# LCD.net
KiCad netlist of a schematic drawn in Altium Designer
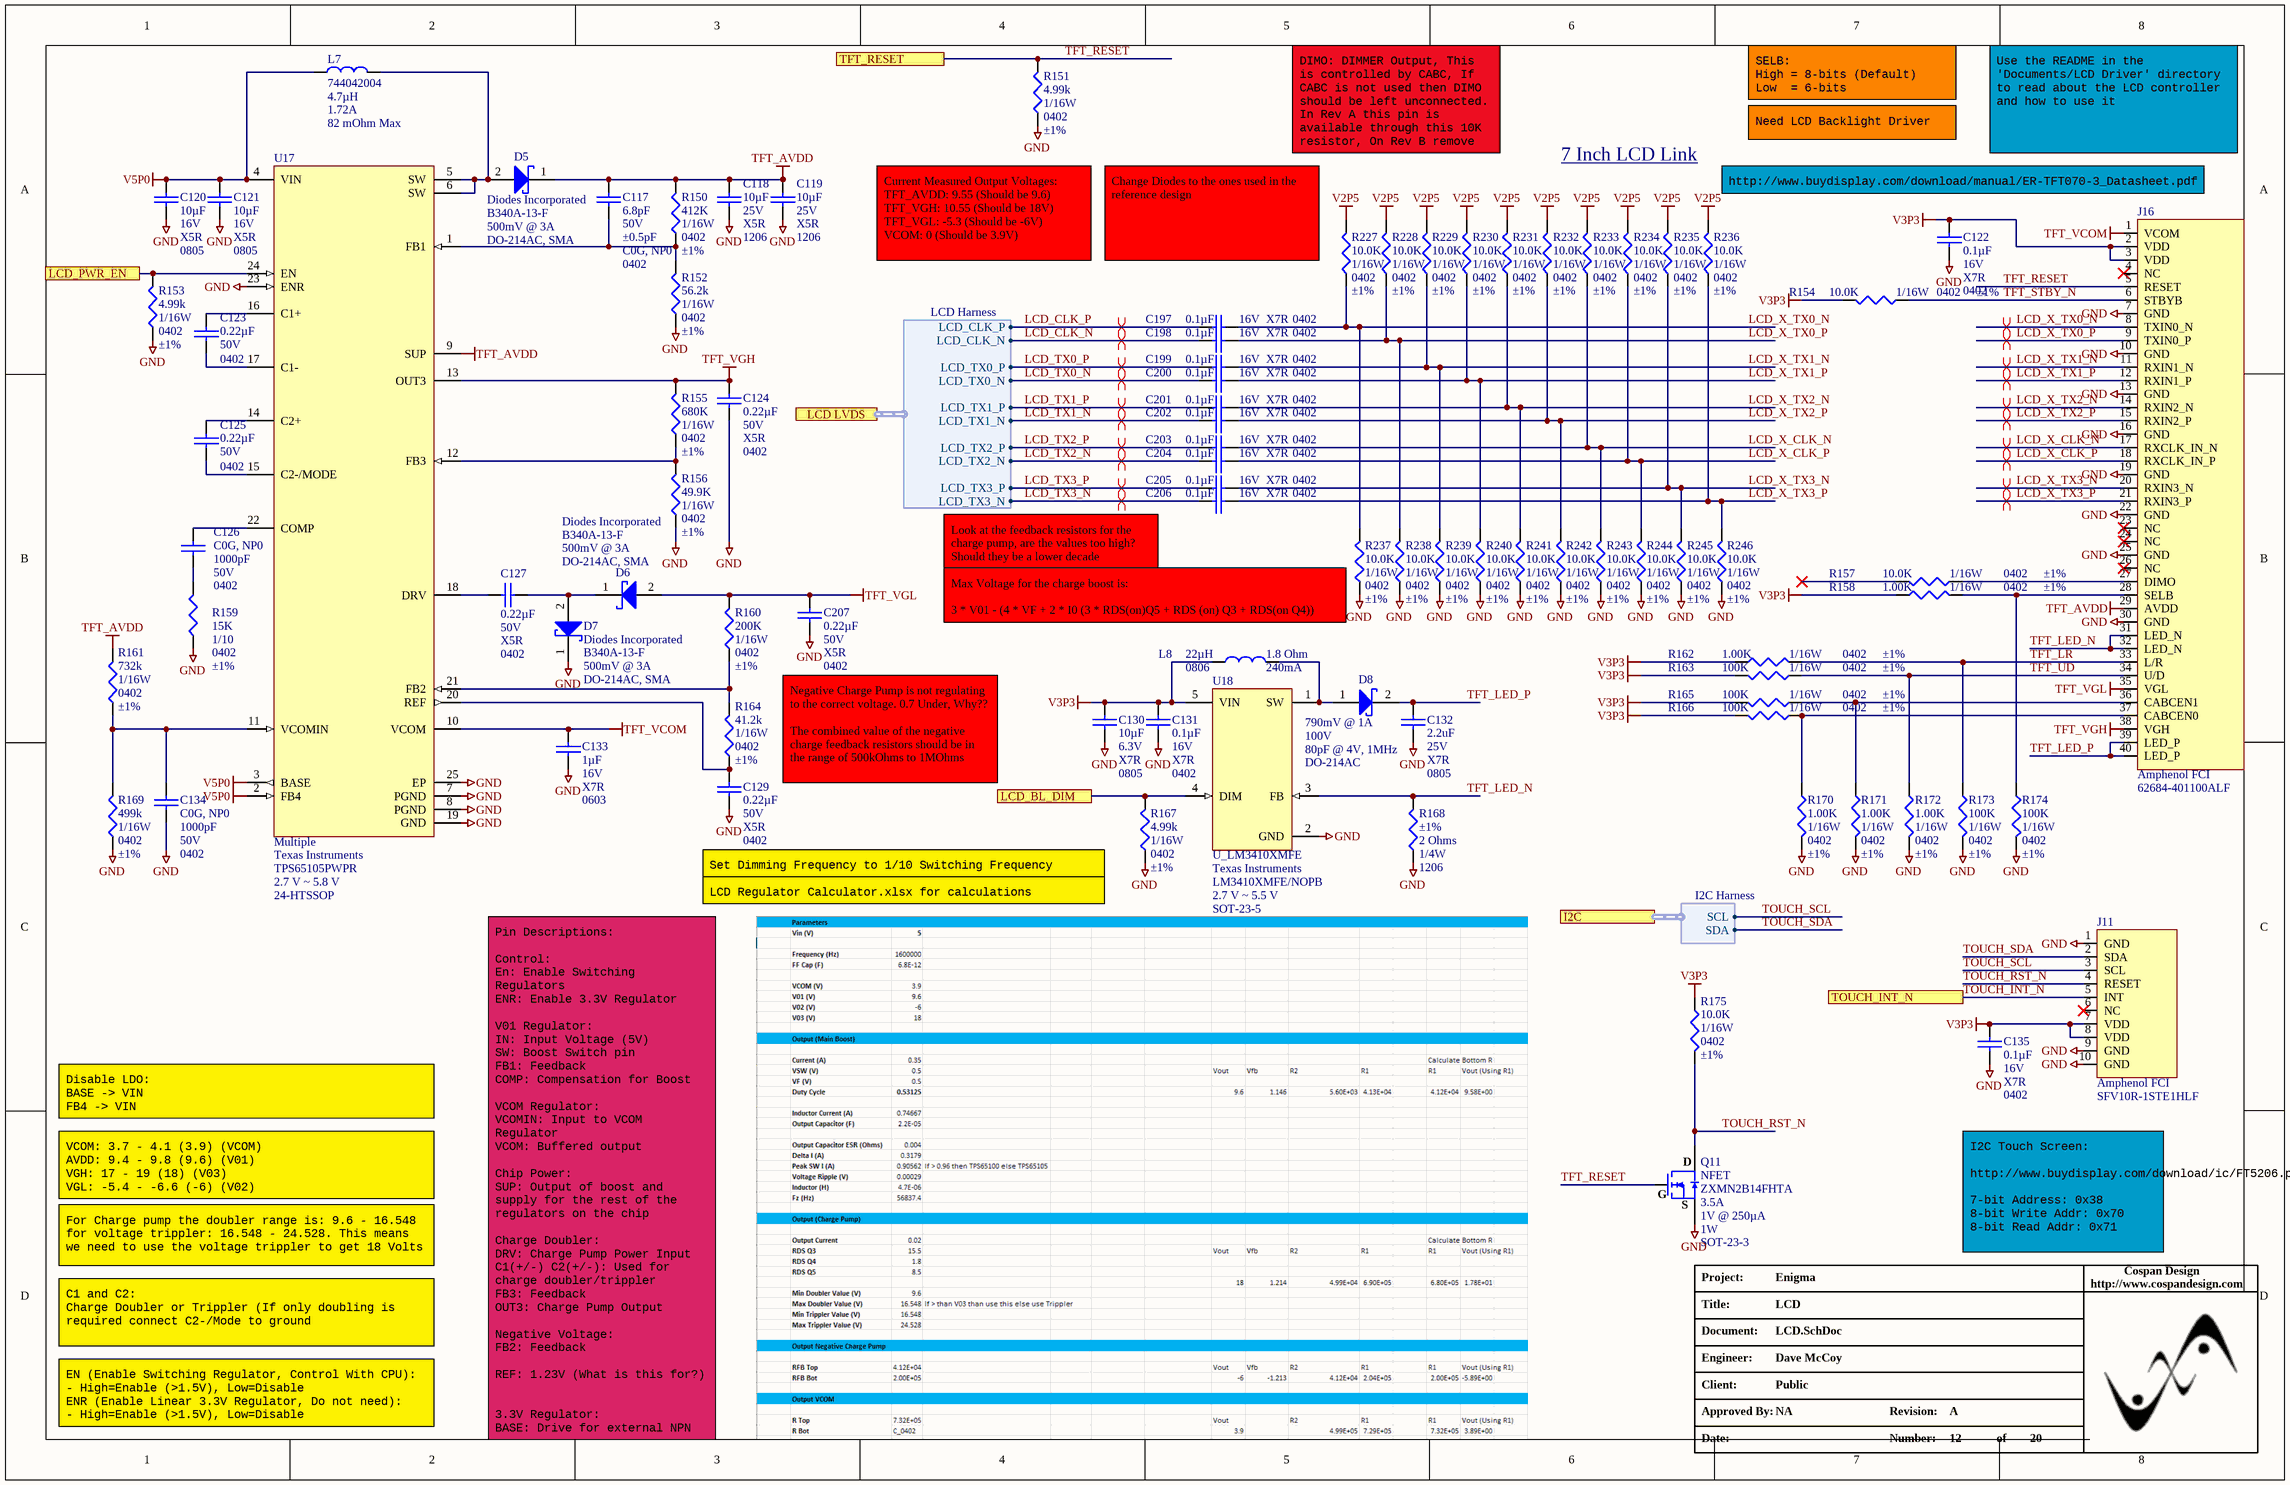
[diagram p0: LCD.SchDoc]

(export (version "E")
  (design (tool "Eeschema 10.0.6"))
  (components
    (comp (ref "C117")
      (value "6.8pF")
      (footprint "C_ERA-0402")
      (description "CAP CER 6.8PF 50V NP0 0402")
      (fields
        (field (name "MANUFACTURER") "Yageo")
        (field (name "MANUFACTURER PART NUMBER") "CC0402DRNPO9BN6R8")
        (field (name "CAPACITANCE") "6.8pF")
        (field (name "VOLTAGE - RATED") "50V")
        (field (name "TOLERANCE") "±0.5pF")
        (field (name "TEMPERATURE COEFFICIENT") "C0G, NP0")
        (field (name "PACKAGE / CASE") "0402")
      )
      (libsource (lib "Main LibraryX") (part "C_0402_6.8PF_50V"))
    )
    (comp (ref "C118")
      (value "10µF")
      (footprint "CAP-1206")
      (description "CAP CER 10UF 25V X5R 1206")
      (fields
        (field (name "MANUFACTURER") "Murata Electronics North America")
        (field (name "MANUFACTURER PART NUMBER") "GRM31CR61E106MA12L")
        (field (name "CAPACITANCE") "10µF")
        (field (name "VOLTAGE - RATED") "25V")
        (field (name "TEMPERATURE COEFFICIENT") "X5R")
        (field (name "PACKAGE / CASE") "1206")
      )
      (libsource (lib "Main Library") (part "C_1206_10UF_25V"))
    )
    (comp (ref "C119")
      (value "10µF")
      (footprint "CAP-1206")
      (description "CAP CER 10UF 25V X5R 1206")
      (fields
        (field (name "MANUFACTURER") "Murata Electronics North America")
        (field (name "MANUFACTURER PART NUMBER") "GRM31CR61E106MA12L")
        (field (name "CAPACITANCE") "10µF")
        (field (name "VOLTAGE - RATED") "25V")
        (field (name "TEMPERATURE COEFFICIENT") "X5R")
        (field (name "PACKAGE / CASE") "1206")
      )
      (libsource (lib "Main Library") (part "C_1206_10UF_25V"))
    )
    (comp (ref "C120")
      (value "10µF")
      (footprint "C_ERA-0805")
      (description "CAP CER 10uF 16V X5R 20% 0805")
      (fields
        (field (name "MANUFACTURER") "Taiyo Yuden")
        (field (name "MANUFACTURER PART NUMBER") "EMK212BJ106KG-T")
        (field (name "CAPACITANCE") "10µF")
        (field (name "VOLTAGE - RATED") "16V")
        (field (name "TEMPERATURE COEFFICIENT") "X5R")
        (field (name "PACKAGE / CASE") "0805")
      )
      (libsource (lib "Main LibraryX") (part "C_0805_10UF_16V"))
    )
    (comp (ref "C121")
      (value "10µF")
      (footprint "C_ERA-0805")
      (description "CAP CER 10uF 16V X5R 20% 0805")
      (fields
        (field (name "MANUFACTURER") "Taiyo Yuden")
        (field (name "MANUFACTURER PART NUMBER") "EMK212BJ106KG-T")
        (field (name "CAPACITANCE") "10µF")
        (field (name "VOLTAGE - RATED") "16V")
        (field (name "TEMPERATURE COEFFICIENT") "X5R")
        (field (name "PACKAGE / CASE") "0805")
      )
      (libsource (lib "Main LibraryX") (part "C_0805_10UF_16V"))
    )
    (comp (ref "C122")
      (value "0.1uF")
      (footprint "C_0402")
      (description "CAP CER .10UF 16V X7R 0402")
      (fields
        (field (name "MANUFACTURER") "Murata Electronics North America")
        (field (name "MANUFACTURER PART NUMBER") "GRM155R71C104KA88J")
        (field (name "CAPACITANCE") "0.1µF")
        (field (name "VOLTAGE - RATED") "16V")
        (field (name "TEMPERATURE COEFFICIENT") "X7R")
        (field (name "PACKAGE / CASE") "0402")
      )
      (libsource (lib "Main LibraryX") (part "C_0402_0.1UF_16V"))
    )
    (comp (ref "C123")
      (value "C_0402_0.22UF_50V")
      (footprint "C_ERA-0402")
      (description "CAP CER 0.22UF 50V X5R 0402")
      (fields
        (field (name "MANUFACTURER") "Taiyo Yuden")
        (field (name "MANUFACTURER PART NUMBER") "UMK105BJ224KV-F")
        (field (name "CAPACITANCE") "0.22µF")
        (field (name "VOLTAGE - RATED") "50V")
        (field (name "PACKAGE / CASE") "0402")
      )
      (libsource (lib "Main Library") (part "C_0402_0.22UF_50V"))
    )
    (comp (ref "C124")
      (value "C_0402_0.22UF_50V")
      (footprint "C_ERA-0402")
      (description "CAP CER 0.22UF 50V X5R 0402")
      (fields
        (field (name "MANUFACTURER") "Taiyo Yuden")
        (field (name "MANUFACTURER PART NUMBER") "UMK105BJ224KV-F")
        (field (name "CAPACITANCE") "0.22µF")
        (field (name "VOLTAGE - RATED") "50V")
        (field (name "TEMPERATURE COEFFICIENT") "X5R")
        (field (name "PACKAGE / CASE") "0402")
      )
      (libsource (lib "Main Library") (part "C_0402_0.22UF_50V"))
    )
    (comp (ref "C125")
      (value "C_0402_0.22UF_50V")
      (footprint "C_ERA-0402")
      (description "CAP CER 0.22UF 50V X5R 0402")
      (fields
        (field (name "MANUFACTURER") "Taiyo Yuden")
        (field (name "MANUFACTURER PART NUMBER") "UMK105BJ224KV-F")
        (field (name "CAPACITANCE") "0.22µF")
        (field (name "VOLTAGE - RATED") "50V")
        (field (name "PACKAGE / CASE") "0402")
      )
      (libsource (lib "Main Library") (part "C_0402_0.22UF_50V"))
    )
    (comp (ref "C126")
      (value "1000pF")
      (footprint "C_ERA-0402")
      (description "CAP CER 1000PF 50V C0G 0402")
      (fields
        (field (name "MANUFACTURER") "Murata Electronics North America")
        (field (name "MANUFACTURER PART NUMBER") "GRM1555C1H102JA01D")
        (field (name "TEMPERATURE COEFFICIENT") "C0G, NP0")
        (field (name "CAPACITANCE") "1000pF")
        (field (name "VOLTAGE - RATED") "50V")
        (field (name "PACKAGE / CASE") "0402")
      )
      (libsource (lib "Main Library") (part "C_0402_1000PF_50V"))
    )
    (comp (ref "C127")
      (value "C_0402_0.22UF_50V")
      (footprint "C_ERA-0402")
      (description "CAP CER 0.22UF 50V X5R 0402")
      (fields
        (field (name "MANUFACTURER") "Taiyo Yuden")
        (field (name "MANUFACTURER PART NUMBER") "UMK105BJ224KV-F")
        (field (name "CAPACITANCE") "0.22µF")
        (field (name "VOLTAGE - RATED") "50V")
        (field (name "TEMPERATURE COEFFICIENT") "X5R")
        (field (name "PACKAGE / CASE") "0402")
      )
      (libsource (lib "Main Library") (part "C_0402_0.22UF_50V"))
    )
    (comp (ref "C129")
      (value "C_0402_0.22UF_50V")
      (footprint "C_ERA-0402")
      (description "CAP CER 0.22UF 50V X5R 0402")
      (fields
        (field (name "MANUFACTURER") "Taiyo Yuden")
        (field (name "MANUFACTURER PART NUMBER") "UMK105BJ224KV-F")
        (field (name "CAPACITANCE") "0.22µF")
        (field (name "VOLTAGE - RATED") "50V")
        (field (name "TEMPERATURE COEFFICIENT") "X5R")
        (field (name "PACKAGE / CASE") "0402")
      )
      (libsource (lib "Main Library") (part "C_0402_0.22UF_50V"))
    )
    (comp (ref "C130")
      (value "10uF")
      (footprint "C_ERA-0805")
      (description "CAP CER 10UF 6.3V X7R 10% 0805")
      (fields
        (field (name "MANUFACTURER") "Taiyo Yuden")
        (field (name "MANUFACTURER PART NUMBER") "JMK212BJ106KD-T")
        (field (name "CAPACITANCE") "10µF")
        (field (name "VOLTAGE - RATED") "6.3V")
        (field (name "TEMPERATURE COEFFICIENT") "X7R")
        (field (name "PACKAGE / CASE") "0805")
      )
      (libsource (lib "Main LibraryX") (part "C_0805_10UF_6.3V"))
    )
    (comp (ref "C131")
      (value "0.1uF")
      (footprint "C_0402")
      (description "CAP CER .10UF 16V X7R 0402")
      (fields
        (field (name "MANUFACTURER") "Murata Electronics North America")
        (field (name "MANUFACTURER PART NUMBER") "GRM155R71C104KA88J")
        (field (name "CAPACITANCE") "0.1µF")
        (field (name "VOLTAGE - RATED") "16V")
        (field (name "TEMPERATURE COEFFICIENT") "X7R")
        (field (name "PACKAGE / CASE") "0402")
      )
      (libsource (lib "Main LibraryX") (part "C_0402_0.1UF_16V"))
    )
    (comp (ref "C132")
      (value "C_0805_2.2uF_25V")
      (footprint "C_ERA-0805")
      (fields
        (field (name "MANUFACTURER") "Taiyo Yuden")
        (field (name "MANUFACTURER PART NUMBER") "TMK212B7225KG-TR")
        (field (name "TOLERANCE") "±10%")
        (field (name "CAPACITANCE") "2.2uF")
        (field (name "VOLTAGE - RATED") "25V")
        (field (name "TEMPERATURE COEFFICIENT") "X7R")
        (field (name "PACKAGE / CASE") "0805")
      )
      (libsource (lib "Cospan Design") (part "C_0805_2.2uF_25V"))
    )
    (comp (ref "C133")
      (value "C_0603_1µF_16V")
      (footprint "C_ERA-0603")
      (description "CAP CER 1UF 16V X7R 0603")
      (fields
        (field (name "MANUFACTURER") "Yageo")
        (field (name "MANUFACTURER PART NUMBER") "CC0603KRX7R7BB105")
        (field (name "CAPACITANCE") "1µF")
        (field (name "VOLTAGE - RATED") "16V")
        (field (name "TEMPERATURE COEFFICIENT") "X7R")
        (field (name "PACKAGE / CASE") "0603")
      )
      (libsource (lib "Cospan Design") (part "C_0603_1µF_16V"))
    )
    (comp (ref "C134")
      (value "1000pF")
      (footprint "C_ERA-0402")
      (description "CAP CER 1000PF 50V C0G 0402")
      (fields
        (field (name "MANUFACTURER") "Murata Electronics North America")
        (field (name "MANUFACTURER PART NUMBER") "GRM1555C1H102JA01D")
        (field (name "TEMPERATURE COEFFICIENT") "C0G, NP0")
        (field (name "CAPACITANCE") "1000pF")
        (field (name "VOLTAGE - RATED") "50V")
        (field (name "PACKAGE / CASE") "0402")
      )
      (libsource (lib "Main Library") (part "C_0402_1000PF_50V"))
    )
    (comp (ref "C135")
      (value "0.1uF")
      (footprint "C_0402")
      (description "CAP CER .10UF 16V X7R 0402")
      (fields
        (field (name "MANUFACTURER") "Murata Electronics North America")
        (field (name "MANUFACTURER PART NUMBER") "GRM155R71C104KA88J")
        (field (name "CAPACITANCE") "0.1µF")
        (field (name "VOLTAGE - RATED") "16V")
        (field (name "TEMPERATURE COEFFICIENT") "X7R")
        (field (name "PACKAGE / CASE") "0402")
      )
      (libsource (lib "Main LibraryX") (part "C_0402_0.1UF_16V"))
    )
    (comp (ref "C197")
      (value "0.1uF")
      (footprint "C_0402")
      (description "CAP CER .10UF 16V X7R 0402")
      (fields
        (field (name "MANUFACTURER") "Murata Electronics North America")
        (field (name "MANUFACTURER PART NUMBER") "GRM155R71C104KA88J")
        (field (name "CAPACITANCE") "0.1µF")
        (field (name "VOLTAGE - RATED") "16V")
        (field (name "TEMPERATURE COEFFICIENT") "X7R")
        (field (name "PACKAGE / CASE") "0402")
      )
      (libsource (lib "Main LibraryX") (part "C_0402_0.1UF_16V"))
    )
    (comp (ref "C198")
      (value "0.1uF")
      (footprint "C_0402")
      (description "CAP CER .10UF 16V X7R 0402")
      (fields
        (field (name "MANUFACTURER") "Murata Electronics North America")
        (field (name "MANUFACTURER PART NUMBER") "GRM155R71C104KA88J")
        (field (name "CAPACITANCE") "0.1µF")
        (field (name "VOLTAGE - RATED") "16V")
        (field (name "TEMPERATURE COEFFICIENT") "X7R")
        (field (name "PACKAGE / CASE") "0402")
      )
      (libsource (lib "Main LibraryX") (part "C_0402_0.1UF_16V"))
    )
    (comp (ref "C199")
      (value "0.1uF")
      (footprint "C_0402")
      (description "CAP CER .10UF 16V X7R 0402")
      (fields
        (field (name "MANUFACTURER") "Murata Electronics North America")
        (field (name "MANUFACTURER PART NUMBER") "GRM155R71C104KA88J")
        (field (name "CAPACITANCE") "0.1µF")
        (field (name "VOLTAGE - RATED") "16V")
        (field (name "TEMPERATURE COEFFICIENT") "X7R")
        (field (name "PACKAGE / CASE") "0402")
      )
      (libsource (lib "Main LibraryX") (part "C_0402_0.1UF_16V"))
    )
    (comp (ref "C200")
      (value "0.1uF")
      (footprint "C_0402")
      (description "CAP CER .10UF 16V X7R 0402")
      (fields
        (field (name "MANUFACTURER") "Murata Electronics North America")
        (field (name "MANUFACTURER PART NUMBER") "GRM155R71C104KA88J")
        (field (name "CAPACITANCE") "0.1µF")
        (field (name "VOLTAGE - RATED") "16V")
        (field (name "TEMPERATURE COEFFICIENT") "X7R")
        (field (name "PACKAGE / CASE") "0402")
      )
      (libsource (lib "Main LibraryX") (part "C_0402_0.1UF_16V"))
    )
    (comp (ref "C201")
      (value "0.1uF")
      (footprint "C_0402")
      (description "CAP CER .10UF 16V X7R 0402")
      (fields
        (field (name "MANUFACTURER") "Murata Electronics North America")
        (field (name "MANUFACTURER PART NUMBER") "GRM155R71C104KA88J")
        (field (name "CAPACITANCE") "0.1µF")
        (field (name "VOLTAGE - RATED") "16V")
        (field (name "TEMPERATURE COEFFICIENT") "X7R")
        (field (name "PACKAGE / CASE") "0402")
      )
      (libsource (lib "Main LibraryX") (part "C_0402_0.1UF_16V"))
    )
    (comp (ref "C202")
      (value "0.1uF")
      (footprint "C_0402")
      (description "CAP CER .10UF 16V X7R 0402")
      (fields
        (field (name "MANUFACTURER") "Murata Electronics North America")
        (field (name "MANUFACTURER PART NUMBER") "GRM155R71C104KA88J")
        (field (name "CAPACITANCE") "0.1µF")
        (field (name "VOLTAGE - RATED") "16V")
        (field (name "TEMPERATURE COEFFICIENT") "X7R")
        (field (name "PACKAGE / CASE") "0402")
      )
      (libsource (lib "Main LibraryX") (part "C_0402_0.1UF_16V"))
    )
    (comp (ref "C203")
      (value "0.1uF")
      (footprint "C_0402")
      (description "CAP CER .10UF 16V X7R 0402")
      (fields
        (field (name "MANUFACTURER") "Murata Electronics North America")
        (field (name "MANUFACTURER PART NUMBER") "GRM155R71C104KA88J")
        (field (name "CAPACITANCE") "0.1µF")
        (field (name "VOLTAGE - RATED") "16V")
        (field (name "TEMPERATURE COEFFICIENT") "X7R")
        (field (name "PACKAGE / CASE") "0402")
      )
      (libsource (lib "Main LibraryX") (part "C_0402_0.1UF_16V"))
    )
    (comp (ref "C204")
      (value "0.1uF")
      (footprint "C_0402")
      (description "CAP CER .10UF 16V X7R 0402")
      (fields
        (field (name "MANUFACTURER") "Murata Electronics North America")
        (field (name "MANUFACTURER PART NUMBER") "GRM155R71C104KA88J")
        (field (name "CAPACITANCE") "0.1µF")
        (field (name "VOLTAGE - RATED") "16V")
        (field (name "TEMPERATURE COEFFICIENT") "X7R")
        (field (name "PACKAGE / CASE") "0402")
      )
      (libsource (lib "Main LibraryX") (part "C_0402_0.1UF_16V"))
    )
    (comp (ref "C205")
      (value "0.1uF")
      (footprint "C_0402")
      (description "CAP CER .10UF 16V X7R 0402")
      (fields
        (field (name "MANUFACTURER") "Murata Electronics North America")
        (field (name "MANUFACTURER PART NUMBER") "GRM155R71C104KA88J")
        (field (name "CAPACITANCE") "0.1µF")
        (field (name "VOLTAGE - RATED") "16V")
        (field (name "TEMPERATURE COEFFICIENT") "X7R")
        (field (name "PACKAGE / CASE") "0402")
      )
      (libsource (lib "Main LibraryX") (part "C_0402_0.1UF_16V"))
    )
    (comp (ref "C206")
      (value "0.1uF")
      (footprint "C_0402")
      (description "CAP CER .10UF 16V X7R 0402")
      (fields
        (field (name "MANUFACTURER") "Murata Electronics North America")
        (field (name "MANUFACTURER PART NUMBER") "GRM155R71C104KA88J")
        (field (name "CAPACITANCE") "0.1µF")
        (field (name "VOLTAGE - RATED") "16V")
        (field (name "TEMPERATURE COEFFICIENT") "X7R")
        (field (name "PACKAGE / CASE") "0402")
      )
      (libsource (lib "Main LibraryX") (part "C_0402_0.1UF_16V"))
    )
    (comp (ref "C207")
      (value "C_0402_0.22UF_50V")
      (footprint "C_ERA-0402")
      (description "CAP CER 0.22UF 50V X5R 0402")
      (fields
        (field (name "MANUFACTURER") "Taiyo Yuden")
        (field (name "MANUFACTURER PART NUMBER") "UMK105BJ224KV-F")
        (field (name "CAPACITANCE") "0.22µF")
        (field (name "VOLTAGE - RATED") "50V")
        (field (name "TEMPERATURE COEFFICIENT") "X5R")
        (field (name "PACKAGE / CASE") "0402")
      )
      (libsource (lib "Main Library") (part "C_0402_0.22UF_50V"))
    )
    (comp (ref "D5")
      (value "D_B340A-13-F")
      (footprint "SMA")
      (description "DIODE SCHOTTKY 40V 3A SMA")
      (fields
        (field (name "MANUFACTURER") "Diodes Incorporated")
        (field (name "MANUFACTURER PART NUMBER") "B340A-13-F")
        (field (name "VOLTAGE - FORWARD (VF) (MAX) @ IF") "500mV @ 3A")
        (field (name "PACKAGE / CASE") "DO-214AC, SMA")
      )
      (libsource (lib "Cospan Design") (part "D_B340A-13-F"))
    )
    (comp (ref "D6")
      (value "D_B340A-13-F")
      (footprint "SMA")
      (description "DIODE SCHOTTKY 40V 3A SMA")
      (fields
        (field (name "MANUFACTURER") "Diodes Incorporated")
        (field (name "MANUFACTURER PART NUMBER") "B340A-13-F")
        (field (name "VOLTAGE - FORWARD (VF) (MAX) @ IF") "500mV @ 3A")
        (field (name "PACKAGE / CASE") "DO-214AC, SMA")
      )
      (libsource (lib "Cospan Design") (part "D_B340A-13-F"))
    )
    (comp (ref "D7")
      (value "D_B340A-13-F")
      (footprint "SMA")
      (description "DIODE SCHOTTKY 40V 3A SMA")
      (fields
        (field (name "MANUFACTURER") "Diodes Incorporated")
        (field (name "MANUFACTURER PART NUMBER") "B340A-13-F")
        (field (name "VOLTAGE - FORWARD (VF) (MAX) @ IF") "500mV @ 3A")
        (field (name "PACKAGE / CASE") "DO-214AC, SMA")
      )
      (libsource (lib "Cospan Design") (part "D_B340A-13-F"))
    )
    (comp (ref "D8")
      (value "B1100-13-F")
      (footprint "DIOM5226X23L")
      (description "DIODE SCHOTTKY 100V 1A SMA")
      (fields
        (field (name "MANUFACTURER") "Diodes Inc")
        (field (name "VOLTAGE - FORWARD (VF) (MAX) @ IF") "790mV @ 1A")
        (field (name "VOLTAGE - DC REVERSE (VR) (MAX)") "100V")
        (field (name "CAPACITANCE @ VR, F") "80pF @ 4V, 1MHz")
        (field (name "PACKAGE / CASE") "DO-214AC")
      )
      (libsource (lib "Main Library") (part "D_SCHOTT_B1100-13-F"))
    )
    (comp (ref "J11")
      (value "J_FFC_CONN_RA_10PIN")
      (footprint "ER-CON10HT-1_BTM")
      (description "CONN FFC BOTTOM 10POS 0.50MM R/A")
      (fields
        (field (name "MANUFACTURER") "Amphenol FCI")
        (field (name "MANUFACTURER PART NUMBER") "SFV10R-1STE1HLF")
      )
      (libsource (lib "Cospan Design") (part "J_FFC_CONN_RA_10PIN"))
    )
    (comp (ref "J16")
      (value "J_FFC_CONN_RA_40PIN")
      (footprint "ER-CON40HT-1_BTM")
      (description "CONN FPC BOTTOM 40POS 0.50MM R/A")
      (fields
        (field (name "MANUFACTURER") "Amphenol FCI")
        (field (name "MANUFACTURER PART NUMBER") "62684-401100ALF")
      )
      (libsource (lib "Cospan Design") (part "J_FFC_CONN_RA_40PIN"))
    )
    (comp (ref "L7")
      (value "4.7uH")
      (footprint "INDP744042006")
      (description "INDUCTOR POWER 4.7UH 1.72A SMD")
      (fields
        (field (name "MANUFACTURER") "Wurth Electronics Inc")
        (field (name "TOLERANCE") "±30%")
        (field (name "MANUFACTURER PART NUMBER") "744042004")
        (field (name "INDUCTANCE") "4.7µH")
        (field (name "CURRENT") "1.72A")
        (field (name "DC RESISTANCE (DCR)") "82 mOhm Max")
      )
      (libsource (lib "Main Library") (part "L_4.70UH_1.72A_SMD"))
    )
    (comp (ref "L8")
      (value "CBC2016T220K")
      (footprint "L_0806")
      (description "INDUCTOR 22UH 10% 0806 SMD")
      (fields
        (field (name "MANUFACTURER") "Taiyo Yuden")
        (field (name "TOLERANCE") "±10%")
        (field (name "CURRENT") "240mA")
        (field (name "PACKAGE / CASE") "0806")
        (field (name "INDUCTANCE") "22µH")
        (field (name "DC RESISTANCE (DCR)") "1.8 Ohm")
      )
      (libsource (lib "Main Library") (part "L_0806_22uH"))
    )
    (comp (ref "Q11")
      (value "NFET")
      (footprint "SOT-23A")
      (description "MOSFET N-CH 20V 3.5A SOT23-3")
      (fields
        (field (name "MANUFACTURER") "Diodes Incorporated")
        (field (name "MANUFACTURER PART NUMBER") "ZXMN2B14FHTA")
        (field (name "CURRENT - CONTINUOUS DRAIN (ID) @ 25° C") "3.5A")
        (field (name "VGS(TH) (MAX) @ ID") "1V @ 250µA")
        (field (name "POWER - MAX") "1W")
        (field (name "PACKAGE / CASE") "SOT-23-3")
      )
      (libsource (lib "Main Library") (part "Q_NFET_3.50A_SOT23"))
    )
    (comp (ref "R150")
      (value "R_0402_412K")
      (footprint "R_0402")
      (fields
        (field (name "RESISTANCE IN OHMS") "412K")
        (field (name "POWER (WATTS)") "1/16W")
        (field (name "CASE") "0402")
        (field (name "TOLERANCE") "±1%")
      )
      (libsource (lib "Cospan Design") (part "R_0402_412K"))
    )
    (comp (ref "R151")
      (value "4.99k")
      (footprint "R_0402")
      (description "RES TF 4.99K OHM 1% 1/16W 0402")
      (fields
        (field (name "MANUFACTURER") "Stackpole Electronics Inc")
        (field (name "MANUFACTURER PART NUMBER") "RMCF0402FT4K99")
        (field (name "RESISTANCE IN OHMS") "4.99k")
        (field (name "POWER (WATTS)") "1/16W")
        (field (name "CASE") "0402")
        (field (name "TOLERANCE") "±1%")
      )
      (libsource (lib "Main Library") (part "R_0402_4.99k"))
    )
    (comp (ref "R152")
      (value "56.2k")
      (footprint "R_0402")
      (description "RES 56.2K OHM 1/16W 1% 0402 SMD")
      (fields
        (field (name "MANUFACTURER") "Vishay Dale")
        (field (name "MANUFACTURER PART NUMBER") "CRCW040256K2FKED")
        (field (name "RESISTANCE IN OHMS") "56.2k")
        (field (name "POWER (WATTS)") "1/16W")
        (field (name "CASE") "0402")
        (field (name "TOLERANCE") "±1%")
      )
      (libsource (lib "Main Library") (part "R_0402_56.2k"))
    )
    (comp (ref "R153")
      (value "4.99k")
      (footprint "R_0402")
      (description "RES TF 4.99K OHM 1% 1/16W 0402")
      (fields
        (field (name "MANUFACTURER") "Stackpole Electronics Inc")
        (field (name "MANUFACTURER PART NUMBER") "RMCF0402FT4K99")
        (field (name "RESISTANCE IN OHMS") "4.99k")
        (field (name "POWER (WATTS)") "1/16W")
        (field (name "CASE") "0402")
        (field (name "TOLERANCE") "±1%")
      )
      (libsource (lib "Main Library") (part "R_0402_4.99k"))
    )
    (comp (ref "R154")
      (value "R_0402_10.0K")
      (footprint "R_0402")
      (description "RES 10.0K OHM 1/16W 1% 0402 SMD")
      (fields
        (field (name "MANUFACTURER") "Stackpole Electronics Inc")
        (field (name "MANUFACTURER PART NUMBER") "RMCF0402FT10K0")
        (field (name "RESISTANCE IN OHMS") "10.0K")
        (field (name "POWER (WATTS)") "1/16W")
        (field (name "CASE") "0402")
        (field (name "TOLERANCE") "±1%")
      )
      (libsource (lib "Cospan Design") (part "R_0402_10.0K"))
    )
    (comp (ref "R155")
      (value "R_0402_680K")
      (footprint "R_0402")
      (description "Res Thick Film 0402 68K Ohm 1% 0.1W(1/10W) Â±100ppm/Â°C Molded SMD Automotive Punched T/R")
      (fields
        (field (name "MANUFACTURER") "Yageo")
        (field (name "MANUFACTURER PART NUMBER") "RC0402FR-07680KL")
        (field (name "RESISTANCE IN OHMS") "680K")
        (field (name "POWER (WATTS)") "1/16W")
        (field (name "CASE") "0402")
        (field (name "TOLERANCE") "±1%")
      )
      (libsource (lib "Cospan Design") (part "R_0402_680K"))
    )
    (comp (ref "R156")
      (value "R_0402_49.9K")
      (footprint "R_0402")
      (description "RES 49.9K OHM 1/16W 1% 0402 SMD")
      (fields
        (field (name "MANUFACTURER") "Vishay Dale")
        (field (name "MANUFACTURER PART NUMBER") "CRCW040249K9FKED")
        (field (name "RESISTANCE IN OHMS") "49.9K")
        (field (name "POWER (WATTS)") "1/16W")
        (field (name "CASE") "0402")
        (field (name "TOLERANCE") "±1%")
      )
      (libsource (lib "Main LibraryX") (part "R_0402_49.9K"))
    )
    (comp (ref "R157")
      (value "R_0402_10.0K")
      (footprint "R_0402")
      (description "RES 10.0K OHM 1/16W 1% 0402 SMD")
      (fields
        (field (name "MANUFACTURER") "Stackpole Electronics Inc")
        (field (name "MANUFACTURER PART NUMBER") "RMCF0402FT10K0")
        (field (name "RESISTANCE IN OHMS") "10.0K")
        (field (name "POWER (WATTS)") "1/16W")
        (field (name "CASE") "0402")
        (field (name "TOLERANCE") "±1%")
      )
      (libsource (lib "Cospan Design") (part "R_0402_10.0K"))
    )
    (comp (ref "R158")
      (value "1.0k Ohms")
      (footprint "R_0402")
      (description "RES 1.00K OHM 1/16W 1% 0402 SMD")
      (fields
        (field (name "MANUFACTURER") "Yageo")
        (field (name "MANUFACTURER PART NUMBER") "RC0402FR-071KL")
        (field (name "RESISTANCE IN OHMS") "1.00K")
        (field (name "POWER (WATTS)") "1/16W")
        (field (name "CASE") "0402")
        (field (name "TOLERANCE") "±1%")
      )
      (libsource (lib "Cospan Design") (part "R_0402_1.0K"))
    )
    (comp (ref "R159")
      (value "R_0402_15.0K")
      (footprint "R_0402")
      (description "RES 15.0K OHM 1/10W 1% 0402 SMD")
      (fields
        (field (name "MANUFACTURER") "Panasonic - ECG")
        (field (name "MANUFACTURER PART NUMBER") "ERJ-2RKF1502X")
        (field (name "RESISTANCE IN OHMS") "15K")
        (field (name "POWER (WATTS)") "1/10")
        (field (name "CASE") "0402")
        (field (name "TOLERANCE") "±1%")
      )
      (libsource (lib "Main Library") (part "R_0402_15.0K"))
    )
    (comp (ref "R160")
      (value "R_0402_200.0K")
      (footprint "R_0402")
      (description "RES 200K OHM 1/16W 1% 0402 SMD")
      (fields
        (field (name "MANUFACTURER") "Yageo")
        (field (name "MANUFACTURER PART NUMBER") "RC0402FR-07200KL")
        (field (name "RESISTANCE IN OHMS") "200K")
        (field (name "POWER (WATTS)") "1/16W")
        (field (name "CASE") "0402")
        (field (name "TOLERANCE") "±1%")
      )
      (libsource (lib "Main Library") (part "R_0402_200.0K"))
    )
    (comp (ref "R161")
      (value "R_0402_732k")
      (footprint "R_0402")
      (description "RES SMD 732K OHM 1% 1/16W 0402")
      (fields
        (field (name "MANUFACTURER") "Yageo")
        (field (name "MANUFACTURER PART NUMBER") "RC0402FR-07732KL")
        (field (name "RESISTANCE IN OHMS") "732k")
        (field (name "POWER (WATTS)") "1/16W")
        (field (name "CASE") "0402")
        (field (name "TOLERANCE") "±1%")
      )
      (libsource (lib "Cospan Design") (part "R_0402_732k"))
    )
    (comp (ref "R162")
      (value "1.0k Ohms")
      (footprint "R_0402")
      (description "RES 1.00K OHM 1/16W 1% 0402 SMD")
      (fields
        (field (name "MANUFACTURER") "Yageo")
        (field (name "MANUFACTURER PART NUMBER") "RC0402FR-071KL")
        (field (name "RESISTANCE IN OHMS") "1.00K")
        (field (name "POWER (WATTS)") "1/16W")
        (field (name "CASE") "0402")
        (field (name "TOLERANCE") "±1%")
      )
      (libsource (lib "Cospan Design") (part "R_0402_1.0K"))
    )
    (comp (ref "R163")
      (value "R_0402_100K")
      (footprint "R_0402")
      (description "RES SMD 100K OHM 1% 1/16W 0402")
      (fields
        (field (name "MANUFACTURER") "Yageo")
        (field (name "MANUFACTURER PART NUMBER") "RC0402FR-07100KL")
        (field (name "RESISTANCE IN OHMS") "100K")
        (field (name "POWER (WATTS)") "1/16W")
        (field (name "CASE") "0402")
        (field (name "TOLERANCE") "±1%")
      )
      (libsource (lib "Cospan Design") (part "R_0402_100K"))
    )
    (comp (ref "R164")
      (value "R_0402_41.2K")
      (footprint "R_0402")
      (description "RES SMD 41.2K OHM 1% 1/16W 0402")
      (fields
        (field (name "RESISTANCE IN OHMS") "41.2k")
        (field (name "POWER (WATTS)") "1/16W")
        (field (name "CASE") "0402")
        (field (name "TOLERANCE") "±1%")
        (field (name "MANUFACTURER") "Yageo")
        (field (name "MANUFACTURER PART NUMBER") "RC0402FR-0741K2L")
      )
      (libsource (lib "Cospan Design") (part "R_0402_41.2K"))
    )
    (comp (ref "R165")
      (value "R_0402_100K")
      (footprint "R_0402")
      (description "RES SMD 100K OHM 1% 1/16W 0402")
      (fields
        (field (name "MANUFACTURER") "Yageo")
        (field (name "MANUFACTURER PART NUMBER") "RC0402FR-07100KL")
        (field (name "RESISTANCE IN OHMS") "100K")
        (field (name "POWER (WATTS)") "1/16W")
        (field (name "CASE") "0402")
        (field (name "TOLERANCE") "±1%")
      )
      (libsource (lib "Cospan Design") (part "R_0402_100K"))
    )
    (comp (ref "R166")
      (value "R_0402_100K")
      (footprint "R_0402")
      (description "RES SMD 100K OHM 1% 1/16W 0402")
      (fields
        (field (name "MANUFACTURER") "Yageo")
        (field (name "MANUFACTURER PART NUMBER") "RC0402FR-07100KL")
        (field (name "RESISTANCE IN OHMS") "100K")
        (field (name "POWER (WATTS)") "1/16W")
        (field (name "CASE") "0402")
        (field (name "TOLERANCE") "±1%")
      )
      (libsource (lib "Cospan Design") (part "R_0402_100K"))
    )
    (comp (ref "R167")
      (value "4.99k")
      (footprint "R_0402")
      (description "RES TF 4.99K OHM 1% 1/16W 0402")
      (fields
        (field (name "MANUFACTURER") "Stackpole Electronics Inc")
        (field (name "MANUFACTURER PART NUMBER") "RMCF0402FT4K99")
        (field (name "RESISTANCE IN OHMS") "4.99k")
        (field (name "POWER (WATTS)") "1/16W")
        (field (name "CASE") "0402")
        (field (name "TOLERANCE") "±1%")
      )
      (libsource (lib "Main Library") (part "R_0402_4.99k"))
    )
    (comp (ref "R168")
      (value "R_1206_2")
      (footprint "R_1206")
      (description "RES SMD 2 OHM 1% 1/4W 1206")
      (fields
        (field (name "MANUFACTURER") "Yageo")
        (field (name "MANUFACTURER PART NUMBER") "RC1206FR-072RL")
        (field (name "TOLERANCE") "±1%")
        (field (name "RESISTANCE IN OHMS") "2 Ohms")
        (field (name "POWER (WATTS)") "1/4W")
        (field (name "CASE") "1206")
      )
      (libsource (lib "Cospan Design") (part "R_1206_2"))
    )
    (comp (ref "R169")
      (value "R_0402_499k")
      (footprint "R_0402")
      (description "RES SMD 499K OHM 1% 1/16W 0402")
      (fields
        (field (name "MANUFACTURER") "Yageo")
        (field (name "MANUFACTURER PART NUMBER") "RC0402FR-07499KL")
        (field (name "RESISTANCE IN OHMS") "499k")
        (field (name "POWER (WATTS)") "1/16W")
        (field (name "CASE") "0402")
        (field (name "TOLERANCE") "±1%")
      )
      (libsource (lib "Main Library") (part "R_0402_499k"))
    )
    (comp (ref "R170")
      (value "1.0k Ohms")
      (footprint "R_0402")
      (description "RES 1.00K OHM 1/16W 1% 0402 SMD")
      (fields
        (field (name "MANUFACTURER") "Yageo")
        (field (name "MANUFACTURER PART NUMBER") "RC0402FR-071KL")
        (field (name "RESISTANCE IN OHMS") "1.00K")
        (field (name "POWER (WATTS)") "1/16W")
        (field (name "CASE") "0402")
        (field (name "TOLERANCE") "±1%")
      )
      (libsource (lib "Cospan Design") (part "R_0402_1.0K"))
    )
    (comp (ref "R171")
      (value "1.0k Ohms")
      (footprint "R_0402")
      (description "RES 1.00K OHM 1/16W 1% 0402 SMD")
      (fields
        (field (name "MANUFACTURER") "Yageo")
        (field (name "MANUFACTURER PART NUMBER") "RC0402FR-071KL")
        (field (name "RESISTANCE IN OHMS") "1.00K")
        (field (name "POWER (WATTS)") "1/16W")
        (field (name "CASE") "0402")
        (field (name "TOLERANCE") "±1%")
      )
      (libsource (lib "Cospan Design") (part "R_0402_1.0K"))
    )
    (comp (ref "R172")
      (value "1.0k Ohms")
      (footprint "R_0402")
      (description "RES 1.00K OHM 1/16W 1% 0402 SMD")
      (fields
        (field (name "MANUFACTURER") "Yageo")
        (field (name "MANUFACTURER PART NUMBER") "RC0402FR-071KL")
        (field (name "RESISTANCE IN OHMS") "1.00K")
        (field (name "POWER (WATTS)") "1/16W")
        (field (name "CASE") "0402")
        (field (name "TOLERANCE") "±1%")
      )
      (libsource (lib "Cospan Design") (part "R_0402_1.0K"))
    )
    (comp (ref "R173")
      (value "R_0402_100K")
      (footprint "R_0402")
      (description "RES SMD 100K OHM 1% 1/16W 0402")
      (fields
        (field (name "MANUFACTURER") "Yageo")
        (field (name "MANUFACTURER PART NUMBER") "RC0402FR-07100KL")
        (field (name "RESISTANCE IN OHMS") "100K")
        (field (name "POWER (WATTS)") "1/16W")
        (field (name "CASE") "0402")
        (field (name "TOLERANCE") "±1%")
      )
      (libsource (lib "Cospan Design") (part "R_0402_100K"))
    )
    (comp (ref "R174")
      (value "R_0402_100K")
      (footprint "R_0402")
      (description "RES SMD 100K OHM 1% 1/16W 0402")
      (fields
        (field (name "MANUFACTURER") "Yageo")
        (field (name "MANUFACTURER PART NUMBER") "RC0402FR-07100KL")
        (field (name "RESISTANCE IN OHMS") "100K")
        (field (name "POWER (WATTS)") "1/16W")
        (field (name "CASE") "0402")
        (field (name "TOLERANCE") "±1%")
      )
      (libsource (lib "Cospan Design") (part "R_0402_100K"))
    )
    (comp (ref "R175")
      (value "R_0402_10.0K")
      (footprint "R_0402")
      (description "RES 10.0K OHM 1/16W 1% 0402 SMD")
      (fields
        (field (name "MANUFACTURER") "Stackpole Electronics Inc")
        (field (name "MANUFACTURER PART NUMBER") "RMCF0402FT10K0")
        (field (name "RESISTANCE IN OHMS") "10.0K")
        (field (name "POWER (WATTS)") "1/16W")
        (field (name "CASE") "0402")
        (field (name "TOLERANCE") "±1%")
      )
      (libsource (lib "Cospan Design") (part "R_0402_10.0K"))
    )
    (comp (ref "R227")
      (value "R_0402_10.0K")
      (footprint "R_0402")
      (description "RES 10.0K OHM 1/16W 1% 0402 SMD")
      (fields
        (field (name "MANUFACTURER") "Stackpole Electronics Inc")
        (field (name "MANUFACTURER PART NUMBER") "RMCF0402FT10K0")
        (field (name "RESISTANCE IN OHMS") "10.0K")
        (field (name "POWER (WATTS)") "1/16W")
        (field (name "CASE") "0402")
        (field (name "TOLERANCE") "±1%")
      )
      (libsource (lib "Main Library") (part "R_0402_10.0K"))
    )
    (comp (ref "R228")
      (value "R_0402_10.0K")
      (footprint "R_0402")
      (description "RES 10.0K OHM 1/16W 1% 0402 SMD")
      (fields
        (field (name "MANUFACTURER") "Stackpole Electronics Inc")
        (field (name "MANUFACTURER PART NUMBER") "RMCF0402FT10K0")
        (field (name "RESISTANCE IN OHMS") "10.0K")
        (field (name "POWER (WATTS)") "1/16W")
        (field (name "CASE") "0402")
        (field (name "TOLERANCE") "±1%")
      )
      (libsource (lib "Main Library") (part "R_0402_10.0K"))
    )
    (comp (ref "R229")
      (value "R_0402_10.0K")
      (footprint "R_0402")
      (description "RES 10.0K OHM 1/16W 1% 0402 SMD")
      (fields
        (field (name "MANUFACTURER") "Stackpole Electronics Inc")
        (field (name "MANUFACTURER PART NUMBER") "RMCF0402FT10K0")
        (field (name "RESISTANCE IN OHMS") "10.0K")
        (field (name "POWER (WATTS)") "1/16W")
        (field (name "CASE") "0402")
        (field (name "TOLERANCE") "±1%")
      )
      (libsource (lib "Main Library") (part "R_0402_10.0K"))
    )
    (comp (ref "R230")
      (value "R_0402_10.0K")
      (footprint "R_0402")
      (description "RES 10.0K OHM 1/16W 1% 0402 SMD")
      (fields
        (field (name "MANUFACTURER") "Stackpole Electronics Inc")
        (field (name "MANUFACTURER PART NUMBER") "RMCF0402FT10K0")
        (field (name "RESISTANCE IN OHMS") "10.0K")
        (field (name "POWER (WATTS)") "1/16W")
        (field (name "CASE") "0402")
        (field (name "TOLERANCE") "±1%")
      )
      (libsource (lib "Main Library") (part "R_0402_10.0K"))
    )
    (comp (ref "R231")
      (value "R_0402_10.0K")
      (footprint "R_0402")
      (description "RES 10.0K OHM 1/16W 1% 0402 SMD")
      (fields
        (field (name "MANUFACTURER") "Stackpole Electronics Inc")
        (field (name "MANUFACTURER PART NUMBER") "RMCF0402FT10K0")
        (field (name "RESISTANCE IN OHMS") "10.0K")
        (field (name "POWER (WATTS)") "1/16W")
        (field (name "CASE") "0402")
        (field (name "TOLERANCE") "±1%")
      )
      (libsource (lib "Main Library") (part "R_0402_10.0K"))
    )
    (comp (ref "R232")
      (value "R_0402_10.0K")
      (footprint "R_0402")
      (description "RES 10.0K OHM 1/16W 1% 0402 SMD")
      (fields
        (field (name "MANUFACTURER") "Stackpole Electronics Inc")
        (field (name "MANUFACTURER PART NUMBER") "RMCF0402FT10K0")
        (field (name "RESISTANCE IN OHMS") "10.0K")
        (field (name "POWER (WATTS)") "1/16W")
        (field (name "CASE") "0402")
        (field (name "TOLERANCE") "±1%")
      )
      (libsource (lib "Main Library") (part "R_0402_10.0K"))
    )
    (comp (ref "R233")
      (value "R_0402_10.0K")
      (footprint "R_0402")
      (description "RES 10.0K OHM 1/16W 1% 0402 SMD")
      (fields
        (field (name "MANUFACTURER") "Stackpole Electronics Inc")
        (field (name "MANUFACTURER PART NUMBER") "RMCF0402FT10K0")
        (field (name "RESISTANCE IN OHMS") "10.0K")
        (field (name "POWER (WATTS)") "1/16W")
        (field (name "CASE") "0402")
        (field (name "TOLERANCE") "±1%")
      )
      (libsource (lib "Main Library") (part "R_0402_10.0K"))
    )
    (comp (ref "R234")
      (value "R_0402_10.0K")
      (footprint "R_0402")
      (description "RES 10.0K OHM 1/16W 1% 0402 SMD")
      (fields
        (field (name "MANUFACTURER") "Stackpole Electronics Inc")
        (field (name "MANUFACTURER PART NUMBER") "RMCF0402FT10K0")
        (field (name "RESISTANCE IN OHMS") "10.0K")
        (field (name "POWER (WATTS)") "1/16W")
        (field (name "CASE") "0402")
        (field (name "TOLERANCE") "±1%")
      )
      (libsource (lib "Main Library") (part "R_0402_10.0K"))
    )
    (comp (ref "R235")
      (value "R_0402_10.0K")
      (footprint "R_0402")
      (description "RES 10.0K OHM 1/16W 1% 0402 SMD")
      (fields
        (field (name "MANUFACTURER") "Stackpole Electronics Inc")
        (field (name "MANUFACTURER PART NUMBER") "RMCF0402FT10K0")
        (field (name "RESISTANCE IN OHMS") "10.0K")
        (field (name "POWER (WATTS)") "1/16W")
        (field (name "CASE") "0402")
        (field (name "TOLERANCE") "±1%")
      )
      (libsource (lib "Main Library") (part "R_0402_10.0K"))
    )
    (comp (ref "R236")
      (value "R_0402_10.0K")
      (footprint "R_0402")
      (description "RES 10.0K OHM 1/16W 1% 0402 SMD")
      (fields
        (field (name "MANUFACTURER") "Stackpole Electronics Inc")
        (field (name "MANUFACTURER PART NUMBER") "RMCF0402FT10K0")
        (field (name "RESISTANCE IN OHMS") "10.0K")
        (field (name "POWER (WATTS)") "1/16W")
        (field (name "CASE") "0402")
        (field (name "TOLERANCE") "±1%")
      )
      (libsource (lib "Main Library") (part "R_0402_10.0K"))
    )
    (comp (ref "R237")
      (value "R_0402_10.0K")
      (footprint "R_0402")
      (description "RES 10.0K OHM 1/16W 1% 0402 SMD")
      (fields
        (field (name "MANUFACTURER") "Stackpole Electronics Inc")
        (field (name "MANUFACTURER PART NUMBER") "RMCF0402FT10K0")
        (field (name "RESISTANCE IN OHMS") "10.0K")
        (field (name "POWER (WATTS)") "1/16W")
        (field (name "CASE") "0402")
        (field (name "TOLERANCE") "±1%")
      )
      (libsource (lib "Main Library") (part "R_0402_10.0K"))
    )
    (comp (ref "R238")
      (value "R_0402_10.0K")
      (footprint "R_0402")
      (description "RES 10.0K OHM 1/16W 1% 0402 SMD")
      (fields
        (field (name "MANUFACTURER") "Stackpole Electronics Inc")
        (field (name "MANUFACTURER PART NUMBER") "RMCF0402FT10K0")
        (field (name "RESISTANCE IN OHMS") "10.0K")
        (field (name "POWER (WATTS)") "1/16W")
        (field (name "CASE") "0402")
        (field (name "TOLERANCE") "±1%")
      )
      (libsource (lib "Main Library") (part "R_0402_10.0K"))
    )
    (comp (ref "R239")
      (value "R_0402_10.0K")
      (footprint "R_0402")
      (description "RES 10.0K OHM 1/16W 1% 0402 SMD")
      (fields
        (field (name "MANUFACTURER") "Stackpole Electronics Inc")
        (field (name "MANUFACTURER PART NUMBER") "RMCF0402FT10K0")
        (field (name "RESISTANCE IN OHMS") "10.0K")
        (field (name "POWER (WATTS)") "1/16W")
        (field (name "CASE") "0402")
        (field (name "TOLERANCE") "±1%")
      )
      (libsource (lib "Main Library") (part "R_0402_10.0K"))
    )
    (comp (ref "R240")
      (value "R_0402_10.0K")
      (footprint "R_0402")
      (description "RES 10.0K OHM 1/16W 1% 0402 SMD")
      (fields
        (field (name "MANUFACTURER") "Stackpole Electronics Inc")
        (field (name "MANUFACTURER PART NUMBER") "RMCF0402FT10K0")
        (field (name "RESISTANCE IN OHMS") "10.0K")
        (field (name "POWER (WATTS)") "1/16W")
        (field (name "CASE") "0402")
        (field (name "TOLERANCE") "±1%")
      )
      (libsource (lib "Main Library") (part "R_0402_10.0K"))
    )
    (comp (ref "R241")
      (value "R_0402_10.0K")
      (footprint "R_0402")
      (description "RES 10.0K OHM 1/16W 1% 0402 SMD")
      (fields
        (field (name "MANUFACTURER") "Stackpole Electronics Inc")
        (field (name "MANUFACTURER PART NUMBER") "RMCF0402FT10K0")
        (field (name "RESISTANCE IN OHMS") "10.0K")
        (field (name "POWER (WATTS)") "1/16W")
        (field (name "CASE") "0402")
        (field (name "TOLERANCE") "±1%")
      )
      (libsource (lib "Main Library") (part "R_0402_10.0K"))
    )
    (comp (ref "R242")
      (value "R_0402_10.0K")
      (footprint "R_0402")
      (description "RES 10.0K OHM 1/16W 1% 0402 SMD")
      (fields
        (field (name "MANUFACTURER") "Stackpole Electronics Inc")
        (field (name "MANUFACTURER PART NUMBER") "RMCF0402FT10K0")
        (field (name "RESISTANCE IN OHMS") "10.0K")
        (field (name "POWER (WATTS)") "1/16W")
        (field (name "CASE") "0402")
        (field (name "TOLERANCE") "±1%")
      )
      (libsource (lib "Main Library") (part "R_0402_10.0K"))
    )
    (comp (ref "R243")
      (value "R_0402_10.0K")
      (footprint "R_0402")
      (description "RES 10.0K OHM 1/16W 1% 0402 SMD")
      (fields
        (field (name "MANUFACTURER") "Stackpole Electronics Inc")
        (field (name "MANUFACTURER PART NUMBER") "RMCF0402FT10K0")
        (field (name "RESISTANCE IN OHMS") "10.0K")
        (field (name "POWER (WATTS)") "1/16W")
        (field (name "CASE") "0402")
        (field (name "TOLERANCE") "±1%")
      )
      (libsource (lib "Main Library") (part "R_0402_10.0K"))
    )
    (comp (ref "R244")
      (value "R_0402_10.0K")
      (footprint "R_0402")
      (description "RES 10.0K OHM 1/16W 1% 0402 SMD")
      (fields
        (field (name "MANUFACTURER") "Stackpole Electronics Inc")
        (field (name "MANUFACTURER PART NUMBER") "RMCF0402FT10K0")
        (field (name "RESISTANCE IN OHMS") "10.0K")
        (field (name "POWER (WATTS)") "1/16W")
        (field (name "CASE") "0402")
        (field (name "TOLERANCE") "±1%")
      )
      (libsource (lib "Main Library") (part "R_0402_10.0K"))
    )
    (comp (ref "R245")
      (value "R_0402_10.0K")
      (footprint "R_0402")
      (description "RES 10.0K OHM 1/16W 1% 0402 SMD")
      (fields
        (field (name "MANUFACTURER") "Stackpole Electronics Inc")
        (field (name "MANUFACTURER PART NUMBER") "RMCF0402FT10K0")
        (field (name "RESISTANCE IN OHMS") "10.0K")
        (field (name "POWER (WATTS)") "1/16W")
        (field (name "CASE") "0402")
        (field (name "TOLERANCE") "±1%")
      )
      (libsource (lib "Main Library") (part "R_0402_10.0K"))
    )
    (comp (ref "R246")
      (value "R_0402_10.0K")
      (footprint "R_0402")
      (description "RES 10.0K OHM 1/16W 1% 0402 SMD")
      (fields
        (field (name "MANUFACTURER") "Stackpole Electronics Inc")
        (field (name "MANUFACTURER PART NUMBER") "RMCF0402FT10K0")
        (field (name "RESISTANCE IN OHMS") "10.0K")
        (field (name "POWER (WATTS)") "1/16W")
        (field (name "CASE") "0402")
        (field (name "TOLERANCE") "±1%")
      )
      (libsource (lib "Main Library") (part "R_0402_10.0K"))
    )
    (comp (ref "U17")
      (value "U_TPS65105PWPR")
      (footprint "PWP0024B_L")
      (description "IC LCD SUPPLY TFT QUAD 24HTSSOP")
      (fields
        (field (name "VOLTAGE - OUTPUT") "Multiple")
        (field (name "MANUFACTURER") "Texas Instruments")
        (field (name "MANUFACTURER PART NUMBER") "TPS65105PWPR")
        (field (name "VOLTAGE - INPUT") "2.7 V ~ 5.8 V")
        (field (name "SUPPLIER DEVICE PACKAGE") "24-HTSSOP")
      )
      (libsource (lib "Cospan Design") (part "U_TPS65105PWPR"))
    )
    (comp (ref "U18")
      (value "U_LM3410XMFE")
      (footprint "MF05A_N")
      (description "IC DRVR WT/OLED BCKLT SOT23-5")
      (fields
        (field (name "MANUFACTURER") "Texas Instruments")
        (field (name "MANUFACTURER PART NUMBER") "LM3410XMFE/NOPB")
        (field (name "VOLTAGE - SUPPLY") "2.7 V ~ 5.5 V")
        (field (name "SUPPLIER DEVICE PACKAGE") "SOT-23-5")
      )
      (libsource (lib "Main Library") (part "U_LM3410XMFE"))
    )
  )
  (nets
    (net (code "4") (name "/LCD_BL_DIM") (class "Default")
      (node (ref "R167") (pin "1") (pinfunction "1_1") (pintype "passive"))
      (node (ref "U18") (pin "4") (pinfunction "DIM_4") (pintype "input"))
    )
    (net (code "5") (name "/LCD_CLK_N") (class "Default")
      (node (ref "C198") (pin "2") (pinfunction "2_2") (pintype "passive"))
    )
    (net (code "6") (name "/LCD_CLK_P") (class "Default")
      (node (ref "C197") (pin "2") (pinfunction "2_2") (pintype "passive"))
    )
    (net (code "7") (name "/LCD_PWR_EN") (class "Default")
      (node (ref "R153") (pin "1") (pinfunction "1_1") (pintype "passive"))
      (node (ref "U17") (pin "24") (pinfunction "EN_24") (pintype "input"))
    )
    (net (code "8") (name "/LCD_TX0_N") (class "Default")
      (node (ref "C200") (pin "2") (pinfunction "2_2") (pintype "passive"))
    )
    (net (code "9") (name "/LCD_TX0_P") (class "Default")
      (node (ref "C199") (pin "2") (pinfunction "2_2") (pintype "passive"))
    )
    (net (code "10") (name "/LCD_TX1_N") (class "Default")
      (node (ref "C202") (pin "2") (pinfunction "2_2") (pintype "passive"))
    )
    (net (code "11") (name "/LCD_TX1_P") (class "Default")
      (node (ref "C201") (pin "2") (pinfunction "2_2") (pintype "passive"))
    )
    (net (code "12") (name "/LCD_TX2_N") (class "Default")
      (node (ref "C204") (pin "2") (pinfunction "2_2") (pintype "passive"))
    )
    (net (code "13") (name "/LCD_TX2_P") (class "Default")
      (node (ref "C203") (pin "2") (pinfunction "2_2") (pintype "passive"))
    )
    (net (code "14") (name "/LCD_TX3_N") (class "Default")
      (node (ref "C206") (pin "2") (pinfunction "2_2") (pintype "passive"))
    )
    (net (code "15") (name "/LCD_TX3_P") (class "Default")
      (node (ref "C205") (pin "2") (pinfunction "2_2") (pintype "passive"))
    )
    (net (code "16") (name "/LCD_X_CLK_N") (class "Default")
      (node (ref "C203") (pin "1") (pinfunction "1_1") (pintype "passive"))
      (node (ref "J16") (pin "17") (pinfunction "RXCLK_IN_N_17") (pintype "passive"))
      (node (ref "R233") (pin "2") (pinfunction "2_2") (pintype "passive"))
      (node (ref "R243") (pin "1") (pinfunction "1_1") (pintype "passive"))
    )
    (net (code "17") (name "/LCD_X_CLK_P") (class "Default")
      (node (ref "C204") (pin "1") (pinfunction "1_1") (pintype "passive"))
      (node (ref "J16") (pin "18") (pinfunction "RXCLK_IN_P_18") (pintype "passive"))
      (node (ref "R234") (pin "2") (pinfunction "2_2") (pintype "passive"))
      (node (ref "R244") (pin "1") (pinfunction "1_1") (pintype "passive"))
    )
    (net (code "18") (name "/LCD_X_TX0_N") (class "Default")
      (node (ref "C197") (pin "1") (pinfunction "1_1") (pintype "passive"))
      (node (ref "J16") (pin "8") (pinfunction "TXIN0_N_8") (pintype "passive"))
      (node (ref "R227") (pin "2") (pinfunction "2_2") (pintype "passive"))
      (node (ref "R237") (pin "1") (pinfunction "1_1") (pintype "passive"))
    )
    (net (code "19") (name "/LCD_X_TX0_P") (class "Default")
      (node (ref "C198") (pin "1") (pinfunction "1_1") (pintype "passive"))
      (node (ref "J16") (pin "9") (pinfunction "TXIN0_P_9") (pintype "passive"))
      (node (ref "R228") (pin "2") (pinfunction "2_2") (pintype "passive"))
      (node (ref "R238") (pin "1") (pinfunction "1_1") (pintype "passive"))
    )
    (net (code "20") (name "/LCD_X_TX1_N") (class "Default")
      (node (ref "C199") (pin "1") (pinfunction "1_1") (pintype "passive"))
      (node (ref "J16") (pin "11") (pinfunction "RXIN1_N_11") (pintype "passive"))
      (node (ref "R229") (pin "2") (pinfunction "2_2") (pintype "passive"))
      (node (ref "R239") (pin "1") (pinfunction "1_1") (pintype "passive"))
    )
    (net (code "21") (name "/LCD_X_TX1_P") (class "Default")
      (node (ref "C200") (pin "1") (pinfunction "1_1") (pintype "passive"))
      (node (ref "J16") (pin "12") (pinfunction "RXIN1_P_12") (pintype "passive"))
      (node (ref "R230") (pin "2") (pinfunction "2_2") (pintype "passive"))
      (node (ref "R240") (pin "1") (pinfunction "1_1") (pintype "passive"))
    )
    (net (code "22") (name "/LCD_X_TX2_N") (class "Default")
      (node (ref "C201") (pin "1") (pinfunction "1_1") (pintype "passive"))
      (node (ref "J16") (pin "14") (pinfunction "RXIN2_N_14") (pintype "passive"))
      (node (ref "R231") (pin "2") (pinfunction "2_2") (pintype "passive"))
      (node (ref "R241") (pin "1") (pinfunction "1_1") (pintype "passive"))
    )
    (net (code "23") (name "/LCD_X_TX2_P") (class "Default")
      (node (ref "C202") (pin "1") (pinfunction "1_1") (pintype "passive"))
      (node (ref "J16") (pin "15") (pinfunction "RXIN2_P_15") (pintype "passive"))
      (node (ref "R232") (pin "2") (pinfunction "2_2") (pintype "passive"))
      (node (ref "R242") (pin "1") (pinfunction "1_1") (pintype "passive"))
    )
    (net (code "24") (name "/LCD_X_TX3_N") (class "Default")
      (node (ref "C205") (pin "1") (pinfunction "1_1") (pintype "passive"))
      (node (ref "J16") (pin "20") (pinfunction "RXIN3_N_20") (pintype "passive"))
      (node (ref "R235") (pin "2") (pinfunction "2_2") (pintype "passive"))
      (node (ref "R245") (pin "1") (pinfunction "1_1") (pintype "passive"))
    )
    (net (code "25") (name "/LCD_X_TX3_P") (class "Default")
      (node (ref "C206") (pin "1") (pinfunction "1_1") (pintype "passive"))
      (node (ref "J16") (pin "21") (pinfunction "RXIN3_P_21") (pintype "passive"))
      (node (ref "R236") (pin "2") (pinfunction "2_2") (pintype "passive"))
      (node (ref "R246") (pin "1") (pinfunction "1_1") (pintype "passive"))
    )
    (net (code "26") (name "/TFT_LED_N") (class "Default")
      (node (ref "J16") (pin "31") (pinfunction "LED_N_31") (pintype "passive"))
      (node (ref "J16") (pin "32") (pinfunction "LED_N_32") (pintype "passive"))
      (node (ref "R168") (pin "1") (pinfunction "1_1") (pintype "passive"))
      (node (ref "U18") (pin "3") (pinfunction "FB_3") (pintype "input"))
    )
    (net (code "27") (name "/TFT_LED_P") (class "Default")
      (node (ref "C132") (pin "2") (pinfunction "2_2") (pintype "passive"))
      (node (ref "D8") (pin "2") (pinfunction "K_2") (pintype "passive"))
      (node (ref "J16") (pin "39") (pinfunction "LED_P_39") (pintype "passive"))
      (node (ref "J16") (pin "40") (pinfunction "LED_P_40") (pintype "passive"))
    )
    (net (code "28") (name "/TFT_LR") (class "Default")
      (node (ref "J16") (pin "33") (pinfunction "L/R_33") (pintype "passive"))
      (node (ref "R162") (pin "1") (pinfunction "1_1") (pintype "passive"))
      (node (ref "R173") (pin "2") (pinfunction "2_2") (pintype "passive"))
    )
    (net (code "29") (name "/TFT_RESET") (class "Default")
      (node (ref "J16") (pin "5") (pinfunction "RESET_5") (pintype "passive"))
      (node (ref "Q11") (pin "1") (pinfunction "G_1") (pintype "passive"))
      (node (ref "R151") (pin "1") (pinfunction "1_1") (pintype "passive"))
    )
    (net (code "30") (name "/TFT_STBY_N") (class "Default")
      (node (ref "J16") (pin "6") (pinfunction "STBYB_6") (pintype "passive"))
      (node (ref "R154") (pin "2") (pinfunction "2_2") (pintype "passive"))
    )
    (net (code "31") (name "/TFT_UD") (class "Default")
      (node (ref "J16") (pin "34") (pinfunction "U/D_34") (pintype "passive"))
      (node (ref "R163") (pin "2") (pinfunction "2_2") (pintype "passive"))
      (node (ref "R172") (pin "2") (pinfunction "2_2") (pintype "passive"))
    )
    (net (code "32") (name "/TOUCH_INT_N") (class "Default")
      (node (ref "J11") (pin "5") (pinfunction "INT_5") (pintype "passive"))
    )
    (net (code "33") (name "/TOUCH_RST_N") (class "Default")
      (node (ref "J11") (pin "4") (pinfunction "RESET_4") (pintype "passive"))
      (node (ref "Q11") (pin "3") (pinfunction "D_3") (pintype "passive"))
      (node (ref "R175") (pin "1") (pinfunction "1_1") (pintype "passive"))
    )
    (net (code "34") (name "/TOUCH_SCL") (class "Default")
      (node (ref "J11") (pin "3") (pinfunction "SCL_3") (pintype "passive"))
    )
    (net (code "35") (name "/TOUCH_SDA") (class "Default")
      (node (ref "J11") (pin "2") (pinfunction "SDA_2") (pintype "passive"))
    )
    (net (code "38") (name "GND") (class "Default")
      (node (ref "C118") (pin "1") (pinfunction "1_1") (pintype "passive"))
      (node (ref "C119") (pin "1") (pinfunction "1_1") (pintype "passive"))
      (node (ref "C120") (pin "1") (pinfunction "1_1") (pintype "passive"))
      (node (ref "C121") (pin "1") (pinfunction "1_1") (pintype "passive"))
      (node (ref "C122") (pin "1") (pinfunction "1_1") (pintype "passive"))
      (node (ref "C124") (pin "2") (pinfunction "2_2") (pintype "passive"))
      (node (ref "C129") (pin "1") (pinfunction "1_1") (pintype "passive"))
      (node (ref "C130") (pin "1") (pinfunction "1_1") (pintype "passive"))
      (node (ref "C131") (pin "1") (pinfunction "1_1") (pintype "passive"))
      (node (ref "C132") (pin "1") (pinfunction "1_1") (pintype "passive"))
      (node (ref "C133") (pin "1") (pinfunction "1_1") (pintype "passive"))
      (node (ref "C134") (pin "1") (pinfunction "1_1") (pintype "passive"))
      (node (ref "C135") (pin "1") (pinfunction "1_1") (pintype "passive"))
      (node (ref "C207") (pin "2") (pinfunction "2_2") (pintype "passive"))
      (node (ref "D7") (pin "1") (pinfunction "1_1") (pintype "passive"))
      (node (ref "J11") (pin "1") (pinfunction "GND_1") (pintype "passive"))
      (node (ref "J11") (pin "10") (pinfunction "GND_10") (pintype "passive"))
      (node (ref "J11") (pin "9") (pinfunction "GND_9") (pintype "passive"))
      (node (ref "J16") (pin "10") (pinfunction "GND_10") (pintype "passive"))
      (node (ref "J16") (pin "13") (pinfunction "GND_13") (pintype "passive"))
      (node (ref "J16") (pin "16") (pinfunction "GND_16") (pintype "passive"))
      (node (ref "J16") (pin "19") (pinfunction "GND_19") (pintype "passive"))
      (node (ref "J16") (pin "22") (pinfunction "GND_22") (pintype "passive"))
      (node (ref "J16") (pin "25") (pinfunction "GND_25") (pintype "passive"))
      (node (ref "J16") (pin "30") (pinfunction "GND_30") (pintype "passive"))
      (node (ref "J16") (pin "7") (pinfunction "GND_7") (pintype "passive"))
      (node (ref "Q11") (pin "2") (pinfunction "S_2") (pintype "passive"))
      (node (ref "R151") (pin "2") (pinfunction "2_2") (pintype "passive"))
      (node (ref "R152") (pin "2") (pinfunction "2_2") (pintype "passive"))
      (node (ref "R153") (pin "2") (pinfunction "2_2") (pintype "passive"))
      (node (ref "R156") (pin "2") (pinfunction "2_2") (pintype "passive"))
      (node (ref "R159") (pin "2") (pinfunction "2_2") (pintype "passive"))
      (node (ref "R167") (pin "2") (pinfunction "2_2") (pintype "passive"))
      (node (ref "R168") (pin "2") (pinfunction "2_2") (pintype "passive"))
      (node (ref "R169") (pin "2") (pinfunction "2_2") (pintype "passive"))
      (node (ref "R170") (pin "1") (pinfunction "1_1") (pintype "passive"))
      (node (ref "R171") (pin "1") (pinfunction "1_1") (pintype "passive"))
      (node (ref "R172") (pin "1") (pinfunction "1_1") (pintype "passive"))
      (node (ref "R173") (pin "1") (pinfunction "1_1") (pintype "passive"))
      (node (ref "R174") (pin "1") (pinfunction "1_1") (pintype "passive"))
      (node (ref "R237") (pin "2") (pinfunction "2_2") (pintype "passive"))
      (node (ref "R238") (pin "2") (pinfunction "2_2") (pintype "passive"))
      (node (ref "R239") (pin "2") (pinfunction "2_2") (pintype "passive"))
      (node (ref "R240") (pin "2") (pinfunction "2_2") (pintype "passive"))
      (node (ref "R241") (pin "2") (pinfunction "2_2") (pintype "passive"))
      (node (ref "R242") (pin "2") (pinfunction "2_2") (pintype "passive"))
      (node (ref "R243") (pin "2") (pinfunction "2_2") (pintype "passive"))
      (node (ref "R244") (pin "2") (pinfunction "2_2") (pintype "passive"))
      (node (ref "R245") (pin "2") (pinfunction "2_2") (pintype "passive"))
      (node (ref "R246") (pin "2") (pinfunction "2_2") (pintype "passive"))
      (node (ref "U17") (pin "19") (pinfunction "GND_19") (pintype "power_in"))
      (node (ref "U17") (pin "23") (pinfunction "ENR_23") (pintype "input"))
      (node (ref "U17") (pin "25") (pinfunction "EP_25") (pintype "power_in"))
      (node (ref "U17") (pin "7") (pinfunction "PGND_7") (pintype "power_in"))
      (node (ref "U17") (pin "8") (pinfunction "PGND_8") (pintype "power_in"))
      (node (ref "U18") (pin "2") (pinfunction "GND_2") (pintype "power_in"))
    )
    (net (code "39") (name "Net-(C126-Pad1)") (class "Default")
      (node (ref "C126") (pin "1") (pinfunction "1_1") (pintype "passive"))
      (node (ref "R159") (pin "1") (pinfunction "1_1") (pintype "passive"))
    )
    (net (code "40") (name "Net-(C127-Pad2)") (class "Default")
      (node (ref "C127") (pin "2") (pinfunction "2_2") (pintype "passive"))
      (node (ref "D6") (pin "1") (pinfunction "1_1") (pintype "passive"))
      (node (ref "D7") (pin "2") (pinfunction "2_2") (pintype "passive"))
    )
    (net (code "41") (name "Net-(D5-Pad2)") (class "Default")
      (node (ref "D5") (pin "2") (pinfunction "2_2") (pintype "passive"))
      (node (ref "L7") (pin "2") (pintype "passive"))
      (node (ref "U17") (pin "5") (pinfunction "SW_5") (pintype "power_in"))
      (node (ref "U17") (pin "6") (pinfunction "SW_6") (pintype "power_in"))
    )
    (net (code "42") (name "Net-(D8-A)") (class "Default")
      (node (ref "D8") (pin "1") (pinfunction "A_1") (pintype "passive"))
      (node (ref "L8") (pin "2") (pintype "passive"))
      (node (ref "U18") (pin "1") (pinfunction "SW_1") (pintype "power_in"))
    )
    (net (code "43") (name "Net-(J16-CABCEN0)") (class "Default")
      (node (ref "J16") (pin "37") (pinfunction "CABCEN0_37") (pintype "passive"))
      (node (ref "R166") (pin "2") (pinfunction "2_2") (pintype "passive"))
      (node (ref "R170") (pin "2") (pinfunction "2_2") (pintype "passive"))
    )
    (net (code "44") (name "Net-(J16-CABCEN1)") (class "Default")
      (node (ref "J16") (pin "36") (pinfunction "CABCEN1_36") (pintype "passive"))
      (node (ref "R165") (pin "2") (pinfunction "2_2") (pintype "passive"))
      (node (ref "R171") (pin "2") (pinfunction "2_2") (pintype "passive"))
    )
    (net (code "45") (name "Net-(J16-DIMO)") (class "Default")
      (node (ref "J16") (pin "27") (pinfunction "DIMO_27") (pintype "passive"))
      (node (ref "R157") (pin "2") (pinfunction "2_2") (pintype "passive"))
    )
    (net (code "46") (name "Net-(J16-SELB)") (class "Default")
      (node (ref "J16") (pin "28") (pinfunction "SELB_28") (pintype "passive"))
      (node (ref "R158") (pin "1") (pinfunction "1_1") (pintype "passive"))
      (node (ref "R174") (pin "2") (pinfunction "2_2") (pintype "passive"))
    )
    (net (code "47") (name "Net-(U17-C1+)") (class "Default")
      (node (ref "C123") (pin "1") (pinfunction "1_1") (pintype "passive"))
      (node (ref "U17") (pin "16") (pinfunction "C1+_16") (pintype "passive"))
    )
    (net (code "48") (name "Net-(U17-C1-)") (class "Default")
      (node (ref "C123") (pin "2") (pinfunction "2_2") (pintype "passive"))
      (node (ref "U17") (pin "17") (pinfunction "C1-_17") (pintype "passive"))
    )
    (net (code "49") (name "Net-(U17-C2+)") (class "Default")
      (node (ref "C125") (pin "1") (pinfunction "1_1") (pintype "passive"))
      (node (ref "U17") (pin "14") (pinfunction "C2+_14") (pintype "passive"))
    )
    (net (code "50") (name "Net-(U17-C2-{slash}MODE)") (class "Default")
      (node (ref "C125") (pin "2") (pinfunction "2_2") (pintype "passive"))
      (node (ref "U17") (pin "15") (pinfunction "C2-/MODE_15") (pintype "passive"))
    )
    (net (code "51") (name "Net-(U17-COMP)") (class "Default")
      (node (ref "C126") (pin "2") (pinfunction "2_2") (pintype "passive"))
      (node (ref "U17") (pin "22") (pinfunction "COMP_22") (pintype "passive"))
    )
    (net (code "52") (name "Net-(U17-DRV)") (class "Default")
      (node (ref "C127") (pin "1") (pinfunction "1_1") (pintype "passive"))
      (node (ref "U17") (pin "18") (pinfunction "DRV_18") (pintype "power_in"))
    )
    (net (code "53") (name "Net-(U17-FB1)") (class "Default")
      (node (ref "C117") (pin "1") (pinfunction "1_1") (pintype "passive"))
      (node (ref "R150") (pin "2") (pinfunction "2_2") (pintype "passive"))
      (node (ref "R152") (pin "1") (pinfunction "1_1") (pintype "passive"))
      (node (ref "U17") (pin "1") (pinfunction "FB1_1") (pintype "input"))
    )
    (net (code "54") (name "Net-(U17-FB2)") (class "Default")
      (node (ref "R160") (pin "2") (pinfunction "2_2") (pintype "passive"))
      (node (ref "R164") (pin "1") (pinfunction "1_1") (pintype "passive"))
      (node (ref "U17") (pin "21") (pinfunction "FB2_21") (pintype "input"))
    )
    (net (code "55") (name "Net-(U17-FB3)") (class "Default")
      (node (ref "R155") (pin "2") (pinfunction "2_2") (pintype "passive"))
      (node (ref "R156") (pin "1") (pinfunction "1_1") (pintype "passive"))
      (node (ref "U17") (pin "12") (pinfunction "FB3_12") (pintype "input"))
    )
    (net (code "56") (name "Net-(U17-REF)") (class "Default")
      (node (ref "C129") (pin "2") (pinfunction "2_2") (pintype "passive"))
      (node (ref "R164") (pin "2") (pinfunction "2_2") (pintype "passive"))
      (node (ref "U17") (pin "20") (pinfunction "REF_20") (pintype "output"))
    )
    (net (code "57") (name "Net-(U17-VCOMIN)") (class "Default")
      (node (ref "C134") (pin "2") (pinfunction "2_2") (pintype "passive"))
      (node (ref "R161") (pin "2") (pinfunction "2_2") (pintype "passive"))
      (node (ref "R169") (pin "1") (pinfunction "1_1") (pintype "passive"))
      (node (ref "U17") (pin "11") (pinfunction "VCOMIN_11") (pintype "input"))
    )
    (net (code "58") (name "TFT_AVDD") (class "Default")
      (node (ref "C117") (pin "2") (pinfunction "2_2") (pintype "passive"))
      (node (ref "C118") (pin "2") (pinfunction "2_2") (pintype "passive"))
      (node (ref "C119") (pin "2") (pinfunction "2_2") (pintype "passive"))
      (node (ref "D5") (pin "1") (pinfunction "1_1") (pintype "passive"))
      (node (ref "J16") (pin "29") (pinfunction "AVDD_29") (pintype "passive"))
      (node (ref "R150") (pin "1") (pinfunction "1_1") (pintype "passive"))
      (node (ref "R161") (pin "1") (pinfunction "1_1") (pintype "passive"))
      (node (ref "U17") (pin "9") (pinfunction "SUP_9") (pintype "power_in"))
    )
    (net (code "59") (name "TFT_VCOM") (class "Default")
      (node (ref "C133") (pin "2") (pinfunction "2_2") (pintype "passive"))
      (node (ref "J16") (pin "1") (pinfunction "VCOM_1") (pintype "passive"))
      (node (ref "U17") (pin "10") (pinfunction "VCOM_10") (pintype "power_in"))
    )
    (net (code "60") (name "TFT_VGH") (class "Default")
      (node (ref "C124") (pin "1") (pinfunction "1_1") (pintype "passive"))
      (node (ref "J16") (pin "38") (pinfunction "VGH_38") (pintype "passive"))
      (node (ref "R155") (pin "1") (pinfunction "1_1") (pintype "passive"))
      (node (ref "U17") (pin "13") (pinfunction "OUT3_13") (pintype "power_in"))
    )
    (net (code "61") (name "TFT_VGL") (class "Default")
      (node (ref "C207") (pin "1") (pinfunction "1_1") (pintype "passive"))
      (node (ref "D6") (pin "2") (pinfunction "2_2") (pintype "passive"))
      (node (ref "J16") (pin "35") (pinfunction "VGL_35") (pintype "passive"))
      (node (ref "R160") (pin "1") (pinfunction "1_1") (pintype "passive"))
    )
    (net (code "62") (name "V2P5") (class "Default")
      (node (ref "R227") (pin "1") (pinfunction "1_1") (pintype "passive"))
      (node (ref "R228") (pin "1") (pinfunction "1_1") (pintype "passive"))
      (node (ref "R229") (pin "1") (pinfunction "1_1") (pintype "passive"))
      (node (ref "R230") (pin "1") (pinfunction "1_1") (pintype "passive"))
      (node (ref "R231") (pin "1") (pinfunction "1_1") (pintype "passive"))
      (node (ref "R232") (pin "1") (pinfunction "1_1") (pintype "passive"))
      (node (ref "R233") (pin "1") (pinfunction "1_1") (pintype "passive"))
      (node (ref "R234") (pin "1") (pinfunction "1_1") (pintype "passive"))
      (node (ref "R235") (pin "1") (pinfunction "1_1") (pintype "passive"))
      (node (ref "R236") (pin "1") (pinfunction "1_1") (pintype "passive"))
    )
    (net (code "63") (name "V3P3") (class "Default")
      (node (ref "C122") (pin "2") (pinfunction "2_2") (pintype "passive"))
      (node (ref "C130") (pin "2") (pinfunction "2_2") (pintype "passive"))
      (node (ref "C131") (pin "2") (pinfunction "2_2") (pintype "passive"))
      (node (ref "C135") (pin "2") (pinfunction "2_2") (pintype "passive"))
      (node (ref "J11") (pin "7") (pinfunction "VDD_7") (pintype "passive"))
      (node (ref "J11") (pin "8") (pinfunction "VDD_8") (pintype "passive"))
      (node (ref "J16") (pin "2") (pinfunction "VDD_2") (pintype "passive"))
      (node (ref "J16") (pin "3") (pinfunction "VDD_3") (pintype "passive"))
      (node (ref "L8") (pin "1") (pintype "passive"))
      (node (ref "R154") (pin "1") (pinfunction "1_1") (pintype "passive"))
      (node (ref "R158") (pin "2") (pinfunction "2_2") (pintype "passive"))
      (node (ref "R162") (pin "2") (pinfunction "2_2") (pintype "passive"))
      (node (ref "R163") (pin "1") (pinfunction "1_1") (pintype "passive"))
      (node (ref "R165") (pin "1") (pinfunction "1_1") (pintype "passive"))
      (node (ref "R166") (pin "1") (pinfunction "1_1") (pintype "passive"))
      (node (ref "R175") (pin "2") (pinfunction "2_2") (pintype "passive"))
      (node (ref "U18") (pin "5") (pinfunction "VIN_5") (pintype "power_in"))
    )
    (net (code "64") (name "V5P0") (class "Default")
      (node (ref "C120") (pin "2") (pinfunction "2_2") (pintype "passive"))
      (node (ref "C121") (pin "2") (pinfunction "2_2") (pintype "passive"))
      (node (ref "L7") (pin "1") (pintype "passive"))
      (node (ref "U17") (pin "2") (pinfunction "FB4_2") (pintype "input"))
      (node (ref "U17") (pin "3") (pinfunction "BASE_3") (pintype "output"))
      (node (ref "U17") (pin "4") (pinfunction "VIN_4") (pintype "power_in"))
    )
    (net (code "65") (name "unconnected-(J11-NC-Pad6)") (class "Default")
      (node (ref "J11") (pin "6") (pinfunction "NC_6") (pintype "passive+no_connect"))
    )
    (net (code "66") (name "unconnected-(J16-NC-Pad4)") (class "Default")
      (node (ref "J16") (pin "4") (pinfunction "NC_4") (pintype "passive+no_connect"))
    )
    (net (code "67") (name "unconnected-(J16-NC-Pad23)") (class "Default")
      (node (ref "J16") (pin "23") (pinfunction "NC_23") (pintype "passive+no_connect"))
    )
    (net (code "68") (name "unconnected-(J16-NC-Pad24)") (class "Default")
      (node (ref "J16") (pin "24") (pinfunction "NC_24") (pintype "passive+no_connect"))
    )
    (net (code "69") (name "unconnected-(J16-NC-Pad26)") (class "Default")
      (node (ref "J16") (pin "26") (pinfunction "NC_26") (pintype "passive+no_connect"))
    )
    (net (code "70") (name "unconnected-(R157-Pad1)") (class "Default")
      (node (ref "R157") (pin "1") (pinfunction "1_1") (pintype "passive+no_connect"))
    )
  )
)
